# Sound_MP3-TF-16P.net
KiCad netlist of a schematic drawn in EAGLE
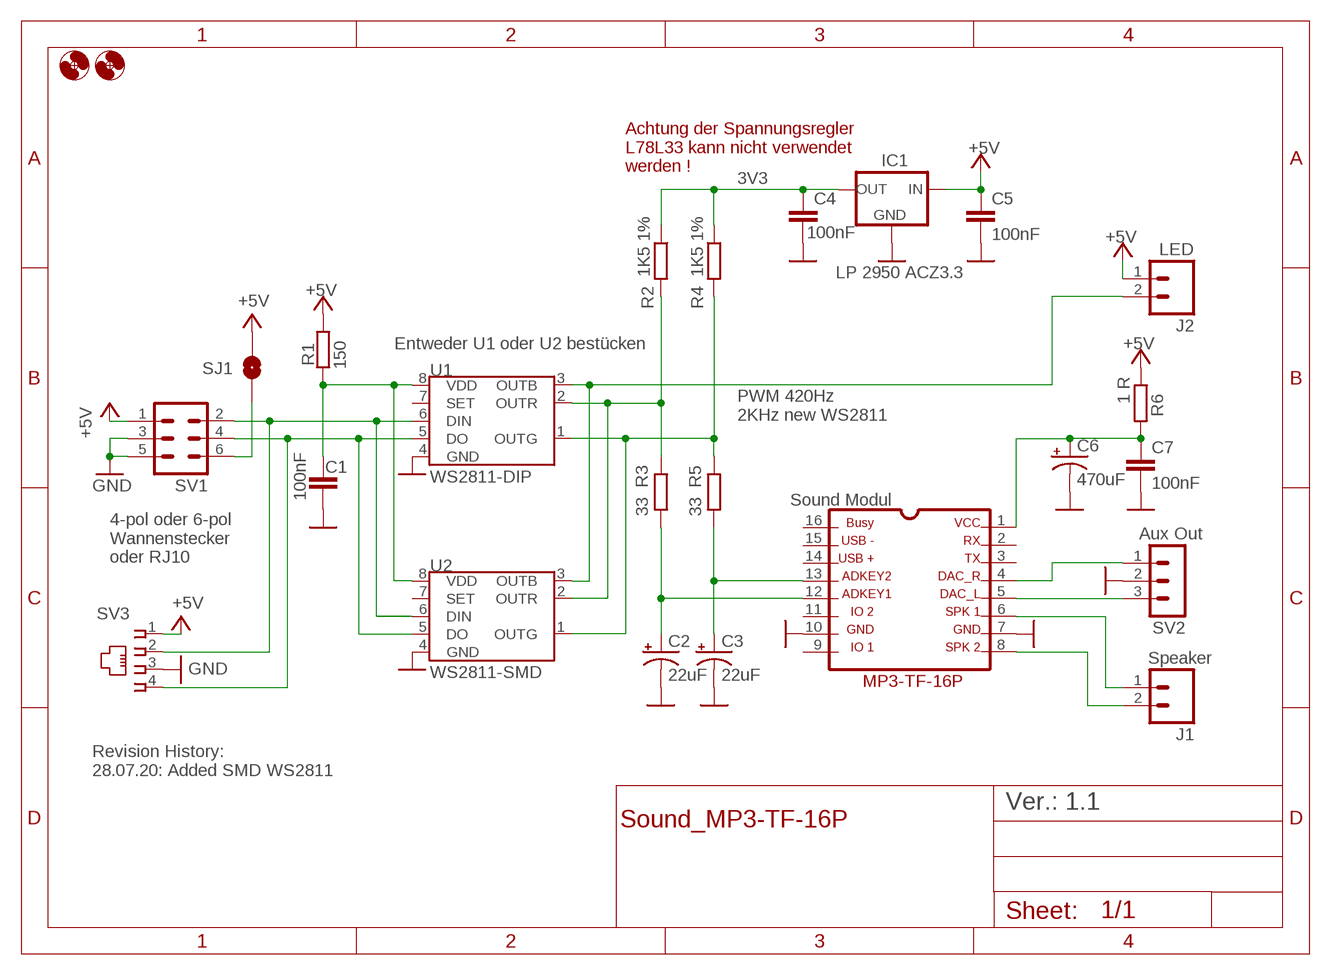
[diagram p0: schematic, sheet 1]

(export (version "E")
  (design (tool "Eeschema 10.0.6"))
  (components
    (comp (ref "C1")
      (value "100nF")
      (footprint "eagle-import:CAP-PTH-SMALL-KIT")
      (libsource (lib "eagle-import") (part "0.1UF-50V-20%(PTH)KIT-EZ"))
    )
    (comp (ref "C2")
      (value "22uF")
      (footprint "eagle-import:CAPACITOR_CPOL-RADIAL-22UF")
      (libsource (lib "eagle-import") (part "CAPACITORS_22UF"))
    )
    (comp (ref "C3")
      (value "22uF")
      (footprint "eagle-import:CAPACITOR_CPOL-RADIAL-22UF")
      (libsource (lib "eagle-import") (part "CAPACITORS_22UF"))
    )
    (comp (ref "C4")
      (value "100nF")
      (footprint "eagle-import:CAP-PTH-SMALL-KIT")
      (libsource (lib "eagle-import") (part "0.1UF-50V-20%(PTH)KIT-EZ"))
    )
    (comp (ref "C5")
      (value "100nF")
      (footprint "eagle-import:CAP-PTH-SMALL-KIT")
      (libsource (lib "eagle-import") (part "0.1UF-50V-20%(PTH)KIT-EZ"))
    )
    (comp (ref "C6")
      (value "470uF")
      (footprint "eagle-import:SPARKFUN-CAPACITORS_CPOL-RADIAL-100UF-25V")
      (libsource (lib "eagle-import") (part "SPARKFUN-CAPACITORS_100UF-25V-20%(PTH)"))
    )
    (comp (ref "C7")
      (value "100nF")
      (footprint "eagle-import:CAP-PTH-SMALL-KIT")
      (libsource (lib "eagle-import") (part "0.1UF-50V-20%(PTH)KIT-EZ"))
    )
    (comp (ref "H1")
      (value "MOUNT-HOLE3.0")
      (footprint "eagle-import:3,0")
      (libsource (lib "eagle-import") (part "MOUNT-HOLE3.0"))
    )
    (comp (ref "H3")
      (value "MOUNT-HOLE3.0")
      (footprint "eagle-import:3,0")
      (libsource (lib "eagle-import") (part "MOUNT-HOLE3.0"))
    )
    (comp (ref "IC1")
      (value "LP 2950 ACZ3.3")
      (footprint "eagle-import:78LXX")
      (libsource (lib "eagle-import") (part "78LXX"))
    )
    (comp (ref "J1")
      (value "Speaker")
      (footprint "eagle-import:1X02")
      (libsource (lib "eagle-import") (part "M02PTH"))
    )
    (comp (ref "J2")
      (value "LED")
      (footprint "eagle-import:1X02")
      (libsource (lib "eagle-import") (part "M02PTH"))
    )
    (comp (ref "MOD1")
      (value "Sound Modul")
      (footprint "eagle-import:MP3-TF-16P_MP3-TF-16P")
      (libsource (lib "eagle-import") (part "MP3-TF-16P_MP3-TF-16P"))
    )
    (comp (ref "R1")
      (value "150")
      (footprint "eagle-import:RCL_0204_5")
      (libsource (lib "eagle-import") (part "RCL_R-EU_0204/5"))
    )
    (comp (ref "R2")
      (value "1K5 1%")
      (footprint "eagle-import:RCL_0204_5")
      (libsource (lib "eagle-import") (part "RCL_R-EU_0204/5"))
    )
    (comp (ref "R3")
      (value "33")
      (footprint "eagle-import:RCL_0204_5")
      (libsource (lib "eagle-import") (part "RCL_R-EU_0204/5"))
    )
    (comp (ref "R4")
      (value "1K5 1%")
      (footprint "eagle-import:RCL_0204_5")
      (libsource (lib "eagle-import") (part "RCL_R-EU_0204/5"))
    )
    (comp (ref "R5")
      (value "33")
      (footprint "eagle-import:RCL_0204_5")
      (libsource (lib "eagle-import") (part "RCL_R-EU_0204/5"))
    )
    (comp (ref "R6")
      (value "1 R")
      (footprint "eagle-import:RCL_0204_5")
      (libsource (lib "eagle-import") (part "RCL_R-EU_0204/5"))
    )
    (comp (ref "SJ1")
      (value "Pin6 = 5V")
      (footprint "eagle-import:SJ_2S-NO")
      (libsource (lib "eagle-import") (part "SOLDERJUMPERNO"))
    )
    (comp (ref "SV1")
      (value "ML6")
      (footprint "eagle-import:ML6")
      (libsource (lib "eagle-import") (part "ML6"))
    )
    (comp (ref "SV2")
      (value "Aux Out")
      (footprint "eagle-import:MA03-1")
      (libsource (lib "eagle-import") (part "MA03-1"))
    )
    (comp (ref "SV3")
      (value "RJ10RJ10_WO_OVERLAP")
      (footprint "eagle-import:RJ10_NO_OVERLAP_BORDER")
      (libsource (lib "eagle-import") (part "RJ10RJ10_WO_OVERLAP"))
    )
    (comp (ref "U1")
      (value "WS2811-DIP")
      (footprint "eagle-import:S3PO_MODUL_WS2811_SOUND_MP3-TF-16P_WS2811_AND_ATTINY_WS2811_DIP08")
      (libsource (lib "eagle-import") (part "S3PO_MODUL_WS2811_SOUND_MP3-TF-16P_WS2811_AND_ATTINY_WS2811-ICTINY45-20-DIP"))
    )
    (comp (ref "U2")
      (value "WS2811-SMD")
      (footprint "eagle-import:S3PO_MODUL_WS2811_SOUND_MP3-TF-16P_WS2811_AND_ATTINY_WS2811_SO08-EIAJ")
      (libsource (lib "eagle-import") (part "S3PO_MODUL_WS2811_SOUND_MP3-TF-16P_WS2811_AND_ATTINY_WS2811-ICTINY45-20-SMT"))
    )
  )
  (nets
    (net (code "1") (name "+5V") (class "Default")
      (node (ref "C5") (pin "1") (pinfunction "1_1") (pintype "passive"))
      (node (ref "IC1") (pin "IN") (pinfunction "IN_IN") (pintype "input"))
      (node (ref "J2") (pin "1") (pinfunction "1_1") (pintype "passive"))
      (node (ref "R1") (pin "2") (pinfunction "2_2") (pintype "passive"))
      (node (ref "R6") (pin "1") (pinfunction "1_1") (pintype "passive"))
      (node (ref "SJ1") (pin "1") (pinfunction "1_1") (pintype "passive"))
      (node (ref "SV1") (pin "1") (pinfunction "1_1") (pintype "passive"))
      (node (ref "SV3") (pin "1") (pinfunction "1_1") (pintype "passive"))
    )
    (net (code "2") (name "/3V3") (class "Default")
      (node (ref "C4") (pin "1") (pinfunction "1_1") (pintype "passive"))
      (node (ref "IC1") (pin "OUT") (pinfunction "OUT_OUT") (pintype "passive"))
      (node (ref "R2") (pin "1") (pinfunction "1_1") (pintype "passive"))
      (node (ref "R4") (pin "1") (pinfunction "1_1") (pintype "passive"))
    )
    (net (code "3") (name "GND") (class "Default")
      (node (ref "C1") (pin "2") (pinfunction "2_2") (pintype "passive"))
      (node (ref "C2") (pin "2") (pinfunction "-_2") (pintype "passive"))
      (node (ref "C3") (pin "2") (pinfunction "-_2") (pintype "passive"))
      (node (ref "C4") (pin "2") (pinfunction "2_2") (pintype "passive"))
      (node (ref "C5") (pin "2") (pinfunction "2_2") (pintype "passive"))
      (node (ref "C6") (pin "2") (pinfunction "-_2") (pintype "passive"))
      (node (ref "C7") (pin "2") (pinfunction "2_2") (pintype "passive"))
      (node (ref "IC1") (pin "GND") (pinfunction "GND_GND") (pintype "input"))
      (node (ref "MOD1") (pin "10") (pinfunction "10_10") (pintype "passive"))
      (node (ref "MOD1") (pin "7") (pinfunction "7_7") (pintype "passive"))
      (node (ref "SV1") (pin "3") (pinfunction "3_3") (pintype "passive"))
      (node (ref "SV1") (pin "5") (pinfunction "5_5") (pintype "passive"))
      (node (ref "SV2") (pin "2") (pinfunction "2_2") (pintype "passive"))
      (node (ref "SV3") (pin "3") (pinfunction "3_3") (pintype "passive"))
      (node (ref "U1") (pin "4") (pinfunction "GND_4") (pintype "power_in"))
      (node (ref "U2") (pin "4") (pinfunction "GND_4") (pintype "power_in"))
    )
    (net (code "4") (name "Net-(C2-+)") (class "Default")
      (node (ref "C2") (pin "1") (pinfunction "+_1") (pintype "passive"))
      (node (ref "MOD1") (pin "12") (pinfunction "12_12") (pintype "passive"))
      (node (ref "R3") (pin "2") (pinfunction "2_2") (pintype "passive"))
    )
    (net (code "5") (name "Net-(C3-+)") (class "Default")
      (node (ref "C3") (pin "1") (pinfunction "+_1") (pintype "passive"))
      (node (ref "MOD1") (pin "13") (pinfunction "13_13") (pintype "passive"))
      (node (ref "R5") (pin "2") (pinfunction "2_2") (pintype "passive"))
    )
    (net (code "6") (name "Net-(C6-+)") (class "Default")
      (node (ref "C6") (pin "1") (pinfunction "+_1") (pintype "passive"))
      (node (ref "C7") (pin "1") (pinfunction "1_1") (pintype "passive"))
      (node (ref "MOD1") (pin "1") (pinfunction "1_1") (pintype "passive"))
      (node (ref "R6") (pin "2") (pinfunction "2_2") (pintype "passive"))
    )
    (net (code "7") (name "Net-(J1-Pad1)") (class "Default")
      (node (ref "J1") (pin "1") (pinfunction "1_1") (pintype "passive"))
      (node (ref "MOD1") (pin "6") (pinfunction "6_6") (pintype "passive"))
    )
    (net (code "8") (name "Net-(J1-Pad2)") (class "Default")
      (node (ref "J1") (pin "2") (pinfunction "2_2") (pintype "passive"))
      (node (ref "MOD1") (pin "8") (pinfunction "8_8") (pintype "passive"))
    )
    (net (code "9") (name "Net-(MOD1-Pad4)") (class "Default")
      (node (ref "MOD1") (pin "4") (pinfunction "4_4") (pintype "passive"))
      (node (ref "SV2") (pin "1") (pinfunction "1_1") (pintype "passive"))
    )
    (net (code "10") (name "Net-(MOD1-Pad5)") (class "Default")
      (node (ref "MOD1") (pin "5") (pinfunction "5_5") (pintype "passive"))
      (node (ref "SV2") (pin "3") (pinfunction "3_3") (pintype "passive"))
    )
    (net (code "11") (name "Net-(SJ1-Pad2)") (class "Default")
      (node (ref "SJ1") (pin "2") (pinfunction "2_2") (pintype "passive"))
      (node (ref "SV1") (pin "6") (pinfunction "6_6") (pintype "passive"))
    )
    (net (code "12") (name "Net-(U1-DIN)") (class "Default")
      (node (ref "SV1") (pin "2") (pinfunction "2_2") (pintype "passive"))
      (node (ref "SV3") (pin "2") (pinfunction "2_2") (pintype "passive"))
      (node (ref "U1") (pin "6") (pinfunction "DIN_6") (pintype "input"))
      (node (ref "U2") (pin "6") (pinfunction "DIN_6") (pintype "input"))
    )
    (net (code "13") (name "Net-(U1-DO)") (class "Default")
      (node (ref "SV1") (pin "4") (pinfunction "4_4") (pintype "passive"))
      (node (ref "SV3") (pin "4") (pinfunction "4_4") (pintype "passive"))
      (node (ref "U1") (pin "5") (pinfunction "DO_5") (pintype "output"))
      (node (ref "U2") (pin "5") (pinfunction "DO_5") (pintype "output"))
    )
    (net (code "14") (name "Net-(U1-OUTB)") (class "Default")
      (node (ref "J2") (pin "2") (pinfunction "2_2") (pintype "passive"))
      (node (ref "U1") (pin "3") (pinfunction "OUTB_3") (pintype "open_collector"))
      (node (ref "U2") (pin "3") (pinfunction "OUTB_3") (pintype "open_collector"))
    )
    (net (code "15") (name "Net-(U1-OUTG)") (class "Default")
      (node (ref "R4") (pin "2") (pinfunction "2_2") (pintype "passive"))
      (node (ref "R5") (pin "1") (pinfunction "1_1") (pintype "passive"))
      (node (ref "U1") (pin "1") (pinfunction "OUTG_1") (pintype "open_collector"))
      (node (ref "U2") (pin "1") (pinfunction "OUTG_1") (pintype "open_collector"))
    )
    (net (code "16") (name "Net-(U1-OUTR)") (class "Default")
      (node (ref "R2") (pin "2") (pinfunction "2_2") (pintype "passive"))
      (node (ref "R3") (pin "1") (pinfunction "1_1") (pintype "passive"))
      (node (ref "U1") (pin "2") (pinfunction "OUTR_2") (pintype "open_collector"))
      (node (ref "U2") (pin "2") (pinfunction "OUTR_2") (pintype "open_collector"))
    )
    (net (code "17") (name "Net-(U1-VDD)") (class "Default")
      (node (ref "C1") (pin "1") (pinfunction "1_1") (pintype "passive"))
      (node (ref "R1") (pin "1") (pinfunction "1_1") (pintype "passive"))
      (node (ref "U1") (pin "8") (pinfunction "VDD_8") (pintype "power_in"))
      (node (ref "U2") (pin "8") (pinfunction "VDD_8") (pintype "power_in"))
    )
    (net (code "18") (name "unconnected-(MOD1-Pad2)") (class "Default")
      (node (ref "MOD1") (pin "2") (pinfunction "2_2") (pintype "passive"))
    )
    (net (code "19") (name "unconnected-(MOD1-Pad3)") (class "Default")
      (node (ref "MOD1") (pin "3") (pinfunction "3_3") (pintype "passive"))
    )
    (net (code "20") (name "unconnected-(MOD1-Pad9)") (class "Default")
      (node (ref "MOD1") (pin "9") (pinfunction "9_9") (pintype "passive"))
    )
    (net (code "21") (name "unconnected-(MOD1-Pad11)") (class "Default")
      (node (ref "MOD1") (pin "11") (pinfunction "11_11") (pintype "passive"))
    )
    (net (code "22") (name "unconnected-(MOD1-Pad14)") (class "Default")
      (node (ref "MOD1") (pin "14") (pinfunction "14_14") (pintype "passive"))
    )
    (net (code "23") (name "unconnected-(MOD1-Pad15)") (class "Default")
      (node (ref "MOD1") (pin "15") (pinfunction "15_15") (pintype "passive"))
    )
    (net (code "24") (name "unconnected-(MOD1-Pad16)") (class "Default")
      (node (ref "MOD1") (pin "16") (pinfunction "16_16") (pintype "passive"))
    )
    (net (code "25") (name "unconnected-(U1-SET-Pad7)") (class "Default")
      (node (ref "U1") (pin "7") (pinfunction "SET_7") (pintype "bidirectional"))
    )
    (net (code "26") (name "unconnected-(U2-SET-Pad7)") (class "Default")
      (node (ref "U2") (pin "7") (pinfunction "SET_7") (pintype "bidirectional"))
    )
  )
)
